# version10_31.net
KiCad netlist of a schematic drawn in EAGLE
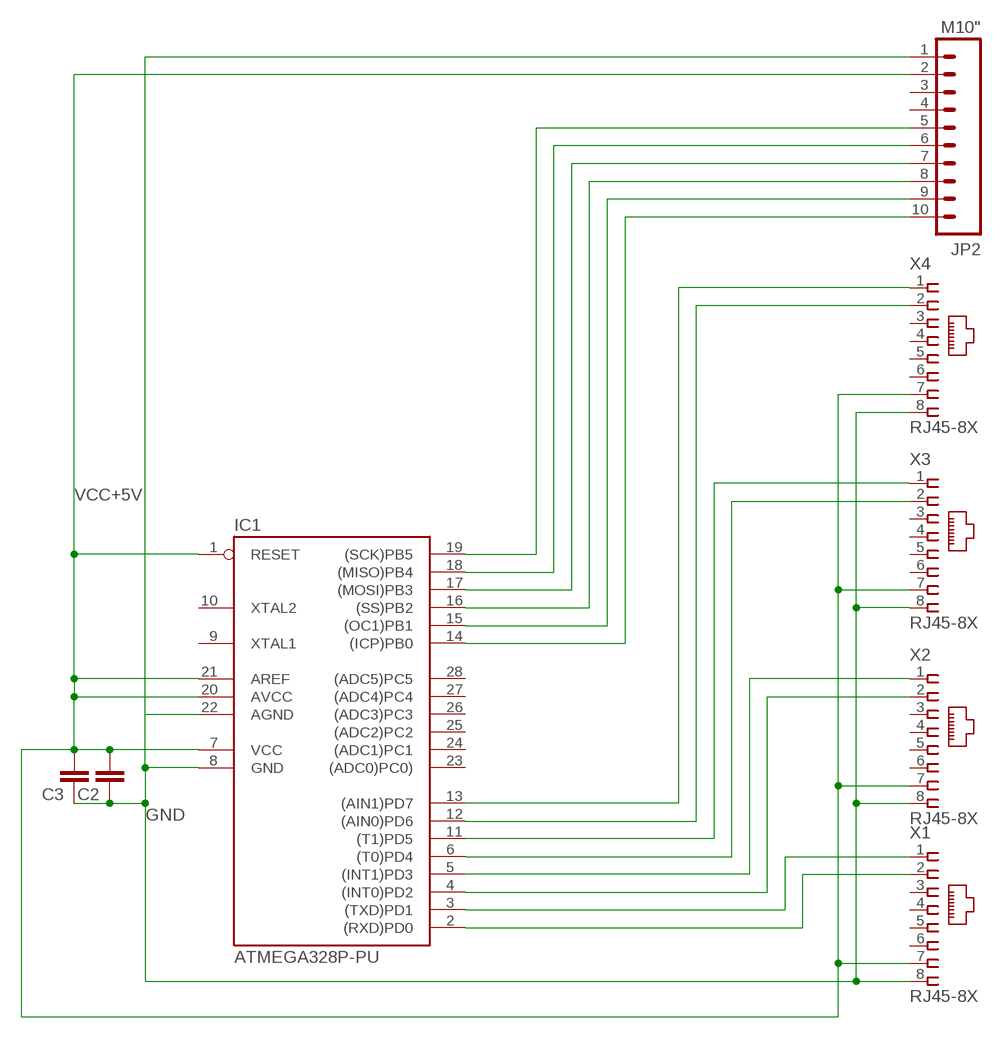
[diagram p0: schematic, sheet 1]

(export (version "E")
  (design (tool "Eeschema 10.0.6"))
  (components
    (comp (ref "C2")
      (value "CAP1206")
      (footprint "eagle-import:1206")
      (libsource (lib "eagle-import") (part "CAP1206"))
    )
    (comp (ref "C3")
      (value "CAP1206")
      (footprint "eagle-import:1206")
      (libsource (lib "eagle-import") (part "CAP1206"))
    )
    (comp (ref "IC1")
      (value "ATMEGA328P-PU")
      (footprint "eagle-import:DIL28-3")
      (libsource (lib "eagle-import") (part "ATMEGA328P-PU"))
    )
    (comp (ref "JP2")
      (value "M10\"")
      (footprint "eagle-import:1X10")
      (libsource (lib "eagle-import") (part "M10{dblquote}"))
    )
    (comp (ref "X1")
      (value "RJ45-8X")
      (footprint "eagle-import:RJ45-NO-SHIELD")
      (libsource (lib "eagle-import") (part "RJ45-8X"))
    )
    (comp (ref "X2")
      (value "RJ45-8X")
      (footprint "eagle-import:RJ45-NO-SHIELD")
      (libsource (lib "eagle-import") (part "RJ45-8X"))
    )
    (comp (ref "X3")
      (value "RJ45-8X")
      (footprint "eagle-import:RJ45-NO-SHIELD")
      (libsource (lib "eagle-import") (part "RJ45-8X"))
    )
    (comp (ref "X4")
      (value "RJ45-8X")
      (footprint "eagle-import:RJ45-NO-SHIELD")
      (libsource (lib "eagle-import") (part "RJ45-8X"))
    )
  )
  (nets
    (net (code "1") (name "/GND") (class "Default")
      (node (ref "C2") (pin "1") (pinfunction "1_1") (pintype "passive"))
      (node (ref "C3") (pin "1") (pinfunction "1_1") (pintype "passive"))
      (node (ref "IC1") (pin "22") (pinfunction "AGND_22") (pintype "power_in"))
      (node (ref "IC1") (pin "8") (pinfunction "GND_8") (pintype "power_in"))
      (node (ref "JP2") (pin "1") (pinfunction "1_1") (pintype "passive"))
      (node (ref "X1") (pin "8") (pinfunction "8_8") (pintype "passive"))
      (node (ref "X2") (pin "8") (pinfunction "8_8") (pintype "passive"))
      (node (ref "X3") (pin "8") (pinfunction "8_8") (pintype "passive"))
      (node (ref "X4") (pin "8") (pinfunction "8_8") (pintype "passive"))
    )
    (net (code "2") (name "/VCC+5V") (class "Default")
      (node (ref "C2") (pin "2") (pinfunction "2_2") (pintype "passive"))
      (node (ref "C3") (pin "2") (pinfunction "2_2") (pintype "passive"))
      (node (ref "IC1") (pin "1") (pinfunction "RESET_1") (pintype "input"))
      (node (ref "IC1") (pin "20") (pinfunction "AVCC_20") (pintype "power_in"))
      (node (ref "IC1") (pin "21") (pinfunction "AREF_21") (pintype "passive"))
      (node (ref "IC1") (pin "7") (pinfunction "VCC_7") (pintype "power_in"))
      (node (ref "JP2") (pin "2") (pinfunction "2_2") (pintype "passive"))
      (node (ref "X1") (pin "7") (pinfunction "7_7") (pintype "passive"))
      (node (ref "X2") (pin "7") (pinfunction "7_7") (pintype "passive"))
      (node (ref "X3") (pin "7") (pinfunction "7_7") (pintype "passive"))
      (node (ref "X4") (pin "7") (pinfunction "7_7") (pintype "passive"))
    )
    (net (code "3") (name "Net-(IC1-(AIN0)PD6)") (class "Default")
      (node (ref "IC1") (pin "12") (pinfunction "(AIN0)PD6_12") (pintype "bidirectional"))
      (node (ref "X4") (pin "2") (pinfunction "2_2") (pintype "passive"))
    )
    (net (code "4") (name "Net-(IC1-(AIN1)PD7)") (class "Default")
      (node (ref "IC1") (pin "13") (pinfunction "(AIN1)PD7_13") (pintype "bidirectional"))
      (node (ref "X4") (pin "1") (pinfunction "1_1") (pintype "passive"))
    )
    (net (code "5") (name "Net-(IC1-(ICP)PB0)") (class "Default")
      (node (ref "IC1") (pin "14") (pinfunction "(ICP)PB0_14") (pintype "bidirectional"))
      (node (ref "JP2") (pin "10") (pinfunction "10_10") (pintype "passive"))
    )
    (net (code "6") (name "Net-(IC1-(INT0)PD2)") (class "Default")
      (node (ref "IC1") (pin "4") (pinfunction "(INT0)PD2_4") (pintype "bidirectional"))
      (node (ref "X2") (pin "2") (pinfunction "2_2") (pintype "passive"))
    )
    (net (code "7") (name "Net-(IC1-(INT1)PD3)") (class "Default")
      (node (ref "IC1") (pin "5") (pinfunction "(INT1)PD3_5") (pintype "bidirectional"))
      (node (ref "X2") (pin "1") (pinfunction "1_1") (pintype "passive"))
    )
    (net (code "8") (name "Net-(IC1-(MISO)PB4)") (class "Default")
      (node (ref "IC1") (pin "18") (pinfunction "(MISO)PB4_18") (pintype "bidirectional"))
      (node (ref "JP2") (pin "6") (pinfunction "6_6") (pintype "passive"))
    )
    (net (code "9") (name "Net-(IC1-(MOSI)PB3)") (class "Default")
      (node (ref "IC1") (pin "17") (pinfunction "(MOSI)PB3_17") (pintype "bidirectional"))
      (node (ref "JP2") (pin "7") (pinfunction "7_7") (pintype "passive"))
    )
    (net (code "10") (name "Net-(IC1-(OC1)PB1)") (class "Default")
      (node (ref "IC1") (pin "15") (pinfunction "(OC1)PB1_15") (pintype "bidirectional"))
      (node (ref "JP2") (pin "9") (pinfunction "9_9") (pintype "passive"))
    )
    (net (code "11") (name "Net-(IC1-(RXD)PD0)") (class "Default")
      (node (ref "IC1") (pin "2") (pinfunction "(RXD)PD0_2") (pintype "bidirectional"))
      (node (ref "X1") (pin "2") (pinfunction "2_2") (pintype "passive"))
    )
    (net (code "12") (name "Net-(IC1-(SCK)PB5)") (class "Default")
      (node (ref "IC1") (pin "19") (pinfunction "(SCK)PB5_19") (pintype "bidirectional"))
      (node (ref "JP2") (pin "5") (pinfunction "5_5") (pintype "passive"))
    )
    (net (code "13") (name "Net-(IC1-(SS)PB2)") (class "Default")
      (node (ref "IC1") (pin "16") (pinfunction "(SS)PB2_16") (pintype "bidirectional"))
      (node (ref "JP2") (pin "8") (pinfunction "8_8") (pintype "passive"))
    )
    (net (code "14") (name "Net-(IC1-(T0)PD4)") (class "Default")
      (node (ref "IC1") (pin "6") (pinfunction "(T0)PD4_6") (pintype "bidirectional"))
      (node (ref "X3") (pin "2") (pinfunction "2_2") (pintype "passive"))
    )
    (net (code "15") (name "Net-(IC1-(T1)PD5)") (class "Default")
      (node (ref "IC1") (pin "11") (pinfunction "(T1)PD5_11") (pintype "bidirectional"))
      (node (ref "X3") (pin "1") (pinfunction "1_1") (pintype "passive"))
    )
    (net (code "16") (name "Net-(IC1-(TXD)PD1)") (class "Default")
      (node (ref "IC1") (pin "3") (pinfunction "(TXD)PD1_3") (pintype "bidirectional"))
      (node (ref "X1") (pin "1") (pinfunction "1_1") (pintype "passive"))
    )
    (net (code "17") (name "unconnected-(IC1-(ADC0)PC0)-Pad23)") (class "Default")
      (node (ref "IC1") (pin "23") (pinfunction "(ADC0)PC0)_23") (pintype "bidirectional"))
    )
    (net (code "18") (name "unconnected-(IC1-(ADC1)PC1-Pad24)") (class "Default")
      (node (ref "IC1") (pin "24") (pinfunction "(ADC1)PC1_24") (pintype "bidirectional"))
    )
    (net (code "19") (name "unconnected-(IC1-(ADC2)PC2-Pad25)") (class "Default")
      (node (ref "IC1") (pin "25") (pinfunction "(ADC2)PC2_25") (pintype "bidirectional"))
    )
    (net (code "20") (name "unconnected-(IC1-(ADC3)PC3-Pad26)") (class "Default")
      (node (ref "IC1") (pin "26") (pinfunction "(ADC3)PC3_26") (pintype "bidirectional"))
    )
    (net (code "21") (name "unconnected-(IC1-(ADC4)PC4-Pad27)") (class "Default")
      (node (ref "IC1") (pin "27") (pinfunction "(ADC4)PC4_27") (pintype "bidirectional"))
    )
    (net (code "22") (name "unconnected-(IC1-(ADC5)PC5-Pad28)") (class "Default")
      (node (ref "IC1") (pin "28") (pinfunction "(ADC5)PC5_28") (pintype "bidirectional"))
    )
    (net (code "23") (name "unconnected-(IC1-XTAL1-Pad9)") (class "Default")
      (node (ref "IC1") (pin "9") (pinfunction "XTAL1_9") (pintype "bidirectional"))
    )
    (net (code "24") (name "unconnected-(IC1-XTAL2-Pad10)") (class "Default")
      (node (ref "IC1") (pin "10") (pinfunction "XTAL2_10") (pintype "bidirectional"))
    )
    (net (code "25") (name "unconnected-(JP2-Pad3)") (class "Default")
      (node (ref "JP2") (pin "3") (pinfunction "3_3") (pintype "passive"))
    )
    (net (code "26") (name "unconnected-(JP2-Pad4)") (class "Default")
      (node (ref "JP2") (pin "4") (pinfunction "4_4") (pintype "passive"))
    )
    (net (code "27") (name "unconnected-(X1-Pad3)") (class "Default")
      (node (ref "X1") (pin "3") (pinfunction "3_3") (pintype "passive"))
    )
    (net (code "28") (name "unconnected-(X1-Pad4)") (class "Default")
      (node (ref "X1") (pin "4") (pinfunction "4_4") (pintype "passive"))
    )
    (net (code "29") (name "unconnected-(X1-Pad5)") (class "Default")
      (node (ref "X1") (pin "5") (pinfunction "5_5") (pintype "passive"))
    )
    (net (code "30") (name "unconnected-(X1-Pad6)") (class "Default")
      (node (ref "X1") (pin "6") (pinfunction "6_6") (pintype "passive"))
    )
    (net (code "31") (name "unconnected-(X2-Pad3)") (class "Default")
      (node (ref "X2") (pin "3") (pinfunction "3_3") (pintype "passive"))
    )
    (net (code "32") (name "unconnected-(X2-Pad4)") (class "Default")
      (node (ref "X2") (pin "4") (pinfunction "4_4") (pintype "passive"))
    )
    (net (code "33") (name "unconnected-(X2-Pad5)") (class "Default")
      (node (ref "X2") (pin "5") (pinfunction "5_5") (pintype "passive"))
    )
    (net (code "34") (name "unconnected-(X2-Pad6)") (class "Default")
      (node (ref "X2") (pin "6") (pinfunction "6_6") (pintype "passive"))
    )
    (net (code "35") (name "unconnected-(X3-Pad3)") (class "Default")
      (node (ref "X3") (pin "3") (pinfunction "3_3") (pintype "passive"))
    )
    (net (code "36") (name "unconnected-(X3-Pad4)") (class "Default")
      (node (ref "X3") (pin "4") (pinfunction "4_4") (pintype "passive"))
    )
    (net (code "37") (name "unconnected-(X3-Pad5)") (class "Default")
      (node (ref "X3") (pin "5") (pinfunction "5_5") (pintype "passive"))
    )
    (net (code "38") (name "unconnected-(X3-Pad6)") (class "Default")
      (node (ref "X3") (pin "6") (pinfunction "6_6") (pintype "passive"))
    )
    (net (code "39") (name "unconnected-(X4-Pad3)") (class "Default")
      (node (ref "X4") (pin "3") (pinfunction "3_3") (pintype "passive"))
    )
    (net (code "40") (name "unconnected-(X4-Pad4)") (class "Default")
      (node (ref "X4") (pin "4") (pinfunction "4_4") (pintype "passive"))
    )
    (net (code "41") (name "unconnected-(X4-Pad5)") (class "Default")
      (node (ref "X4") (pin "5") (pinfunction "5_5") (pintype "passive"))
    )
    (net (code "42") (name "unconnected-(X4-Pad6)") (class "Default")
      (node (ref "X4") (pin "6") (pinfunction "6_6") (pintype "passive"))
    )
  )
)
